# atWork_LCD.net
KiCad netlist of a schematic drawn in Altium Designer
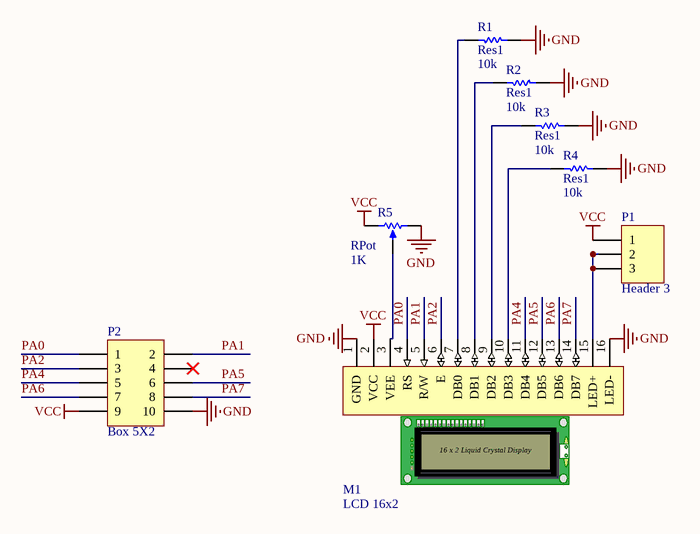
[diagram p0: atWork_LCD.SchDoc]

(export (version "E")
  (design (tool "Eeschema 10.0.6"))
  (components
    (comp (ref "M1")
      (value "LCD 16x2")
      (footprint "LCD16PIN")
      (description "16-pin 16x2 Liquid Crystal Display")
      (fields (field (name "DESIGNER") "Meysam Parvizi") (field (name "EMAIL") "meysam.parvizi.ir@gmail.com"))
      (libsource (lib "mp") (part "LCD 16x2"))
    )
    (comp (ref "P1")
      (value "Header 3")
      (footprint "HDR1X3")
      (description "Header, 3-Pin")
      (fields (field (name "PUBLISHER") "Altium Limited"))
      (libsource (lib "Miscellaneous Connectors") (part "Header 3"))
    )
    (comp (ref "P2")
      (value "Box 5X2")
      (footprint "BOX2X5_RIGHT")
      (description "Box, 5-Pin, Dual row")
      (fields (field (name "DESIGNER") "Meysam Parvizi") (field (name "EMAIL") "meysam.parvizi.ir@gmail.com"))
      (libsource (lib "mp") (part "Box 5X2"))
    )
    (comp (ref "R1")
      (value "Res1")
      (footprint "C1206")
      (description "Resistor")
      (fields (field (name "ALTIUM_VALUE") "10k") (field (name "PUBLISHER") "Altium Limited"))
      (libsource (lib "Miscellaneous Devices") (part "Res1"))
    )
    (comp (ref "R2")
      (value "Res1")
      (footprint "C1206")
      (description "Resistor")
      (fields (field (name "ALTIUM_VALUE") "10k") (field (name "PUBLISHER") "Altium Limited"))
      (libsource (lib "Miscellaneous Devices") (part "Res1"))
    )
    (comp (ref "R3")
      (value "Res1")
      (footprint "C1206")
      (description "Resistor")
      (fields (field (name "ALTIUM_VALUE") "10k") (field (name "PUBLISHER") "Altium Limited"))
      (libsource (lib "Miscellaneous Devices") (part "Res1"))
    )
    (comp (ref "R4")
      (value "Res1")
      (footprint "C1206")
      (description "Resistor")
      (fields (field (name "ALTIUM_VALUE") "10k") (field (name "PUBLISHER") "Altium Limited"))
      (libsource (lib "Miscellaneous Devices") (part "Res1"))
    )
    (comp (ref "R5")
      (value "RPot")
      (footprint "RPOT")
      (description "Potentiometer")
      (fields
        (field (name "ALTIUM_VALUE") "1K")
        (field (name "DESIGNER") "Meysam Parvizi")
        (field (name "EMAIL") "meysam.parvizi.ir@gmail.com")
      )
      (libsource (lib "mp") (part "RPot"))
    )
  )
  (nets
    (net (code "1") (name "/PA0") (class "Default")
      (node (ref "M1") (pin "4") (pinfunction "RS_4") (pintype "input"))
      (node (ref "P2") (pin "1") (pinfunction "1_1") (pintype "passive"))
    )
    (net (code "2") (name "/PA1") (class "Default")
      (node (ref "M1") (pin "5") (pinfunction "R/W_5") (pintype "input"))
      (node (ref "P2") (pin "2") (pinfunction "2_2") (pintype "passive"))
    )
    (net (code "3") (name "/PA2") (class "Default")
      (node (ref "M1") (pin "6") (pinfunction "E_6") (pintype "bidirectional"))
      (node (ref "P2") (pin "3") (pinfunction "3_3") (pintype "passive"))
    )
    (net (code "4") (name "/PA4") (class "Default")
      (node (ref "M1") (pin "11") (pinfunction "DB4_11") (pintype "bidirectional"))
      (node (ref "P2") (pin "5") (pinfunction "5_5") (pintype "passive"))
    )
    (net (code "5") (name "/PA5") (class "Default")
      (node (ref "M1") (pin "12") (pinfunction "DB5_12") (pintype "bidirectional"))
      (node (ref "P2") (pin "6") (pinfunction "6_6") (pintype "passive"))
    )
    (net (code "6") (name "/PA6") (class "Default")
      (node (ref "M1") (pin "13") (pinfunction "DB6_13") (pintype "bidirectional"))
      (node (ref "P2") (pin "7") (pinfunction "7_7") (pintype "passive"))
    )
    (net (code "7") (name "/PA7") (class "Default")
      (node (ref "M1") (pin "14") (pinfunction "DB7_14") (pintype "bidirectional"))
      (node (ref "P2") (pin "8") (pinfunction "8_8") (pintype "passive"))
    )
    (net (code "8") (name "GND") (class "Default")
      (node (ref "M1") (pin "1") (pinfunction "GND_1") (pintype "power_in"))
      (node (ref "M1") (pin "16") (pinfunction "LED-_16") (pintype "passive"))
      (node (ref "P2") (pin "10") (pinfunction "10_10") (pintype "passive"))
      (node (ref "R1") (pin "2") (pinfunction "2_2") (pintype "passive"))
      (node (ref "R2") (pin "2") (pinfunction "2_2") (pintype "passive"))
      (node (ref "R3") (pin "2") (pinfunction "2_2") (pintype "passive"))
      (node (ref "R4") (pin "2") (pinfunction "2_2") (pintype "passive"))
      (node (ref "R5") (pin "2") (pinfunction "BOT_2") (pintype "passive"))
    )
    (net (code "9") (name "Net-(M1-DB0)") (class "Default")
      (node (ref "M1") (pin "7") (pinfunction "DB0_7") (pintype "bidirectional"))
      (node (ref "R1") (pin "1") (pinfunction "1_1") (pintype "passive"))
    )
    (net (code "10") (name "Net-(M1-DB1)") (class "Default")
      (node (ref "M1") (pin "8") (pinfunction "DB1_8") (pintype "bidirectional"))
      (node (ref "R2") (pin "1") (pinfunction "1_1") (pintype "passive"))
    )
    (net (code "11") (name "Net-(M1-DB2)") (class "Default")
      (node (ref "M1") (pin "9") (pinfunction "DB2_9") (pintype "bidirectional"))
      (node (ref "R3") (pin "1") (pinfunction "1_1") (pintype "passive"))
    )
    (net (code "12") (name "Net-(M1-DB3)") (class "Default")
      (node (ref "M1") (pin "10") (pinfunction "DB3_10") (pintype "bidirectional"))
      (node (ref "R4") (pin "1") (pinfunction "1_1") (pintype "passive"))
    )
    (net (code "13") (name "Net-(M1-LED+)") (class "Default")
      (node (ref "M1") (pin "15") (pinfunction "LED+_15") (pintype "passive"))
      (node (ref "P1") (pin "2") (pinfunction "2_2") (pintype "passive"))
      (node (ref "P1") (pin "3") (pinfunction "3_3") (pintype "passive"))
    )
    (net (code "14") (name "Net-(M1-VEE)") (class "Default")
      (node (ref "M1") (pin "3") (pinfunction "VEE_3") (pintype "passive"))
      (node (ref "R5") (pin "3") (pinfunction "TAP_3") (pintype "passive"))
    )
    (net (code "15") (name "VCC") (class "Default")
      (node (ref "M1") (pin "2") (pinfunction "VCC_2") (pintype "power_in"))
      (node (ref "P1") (pin "1") (pinfunction "1_1") (pintype "passive"))
      (node (ref "P2") (pin "9") (pinfunction "9_9") (pintype "passive"))
      (node (ref "R5") (pin "1") (pinfunction "TOP_1") (pintype "passive"))
    )
    (net (code "16") (name "unconnected-(P2-Pad4)") (class "Default")
      (node (ref "P2") (pin "4") (pinfunction "4_4") (pintype "passive+no_connect"))
    )
  )
)
